# sch.net
KiCad netlist of a schematic drawn in Altium Designer
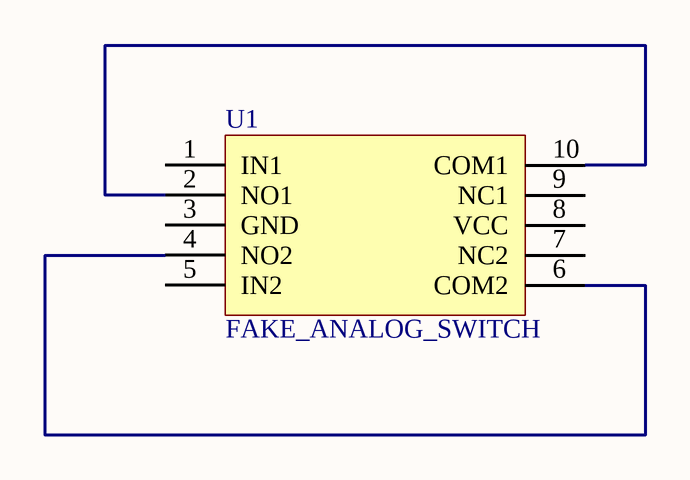
[diagram p0: sch.SchDoc]

(export (version "E")
  (design (tool "Eeschema 10.0.6"))
  (components
    (comp (ref "U1")
      (value "FAKE_ANALOG_SWITCH")
      (footprint "SMTPCB-SPOOF-UFQFN-10")
      (description "I MADE A BAD DESIGN CHOICE AND HAVE TO LIVE WITH IT NOW")
      (libsource (lib "lib") (part "FAKE_ANALOG_SWITCH"))
    )
  )
  (nets
    (net (code "1") (name "Net-(U1-COM1)") (class "Default")
      (node (ref "U1") (pin "10") (pinfunction "COM1_10") (pintype "passive"))
      (node (ref "U1") (pin "2") (pinfunction "NO1_2") (pintype "passive"))
    )
    (net (code "2") (name "Net-(U1-COM2)") (class "Default")
      (node (ref "U1") (pin "4") (pinfunction "NO2_4") (pintype "passive"))
      (node (ref "U1") (pin "6") (pinfunction "COM2_6") (pintype "passive"))
    )
    (net (code "3") (name "unconnected-(U1-GND-Pad3)") (class "Default")
      (node (ref "U1") (pin "3") (pinfunction "GND_3") (pintype "passive"))
    )
    (net (code "4") (name "unconnected-(U1-IN1-Pad1)") (class "Default")
      (node (ref "U1") (pin "1") (pinfunction "IN1_1") (pintype "passive"))
    )
    (net (code "5") (name "unconnected-(U1-IN2-Pad5)") (class "Default")
      (node (ref "U1") (pin "5") (pinfunction "IN2_5") (pintype "passive"))
    )
    (net (code "6") (name "unconnected-(U1-NC1-Pad9)") (class "Default")
      (node (ref "U1") (pin "9") (pinfunction "NC1_9") (pintype "passive"))
    )
    (net (code "7") (name "unconnected-(U1-NC2-Pad7)") (class "Default")
      (node (ref "U1") (pin "7") (pinfunction "NC2_7") (pintype "passive"))
    )
    (net (code "8") (name "unconnected-(U1-VCC-Pad8)") (class "Default")
      (node (ref "U1") (pin "8") (pinfunction "VCC_8") (pintype "passive"))
    )
  )
)
